# wisp-6-peripherals.net
KiCad netlist of a schematic drawn in Altium Designer
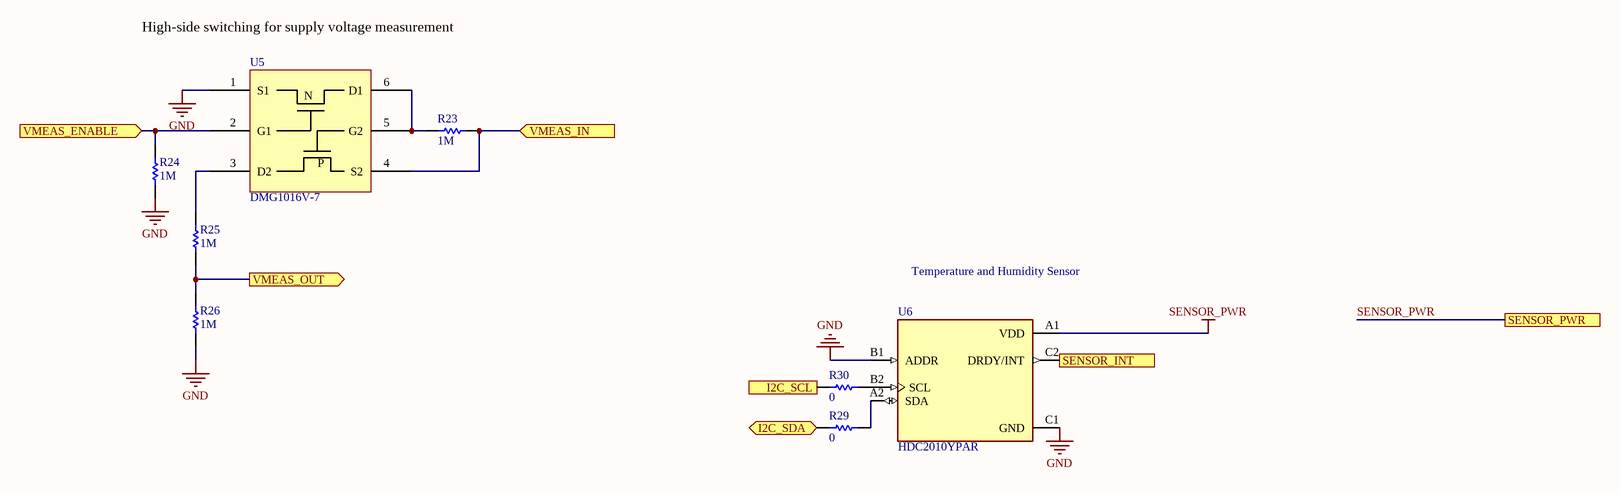
[diagram p0: wisp-6-peripherals.SchDoc]

(export (version "E")
  (design (tool "Eeschema 10.0.6"))
  (components
    (comp (ref "R23")
      (value "1M")
      (footprint "0402")
      (description "RES 1M OHM 5% 1/16W 0402")
      (fields
        (field (name "MANUFACTURER") "YAGEO")
        (field (name "MANUFACTURER PART NUMBER") "RC0402JR-071ML")
      )
      (libsource (lib "WISP6") (part "R-1M-0.063W-5%-0402"))
    )
    (comp (ref "R24")
      (value "1M")
      (footprint "0402")
      (description "RES 1M OHM 5% 1/16W 0402")
      (fields
        (field (name "MANUFACTURER") "YAGEO")
        (field (name "MANUFACTURER PART NUMBER") "RC0402JR-071ML")
      )
      (libsource (lib "WISP6") (part "R-1M-0.063W-5%-0402"))
    )
    (comp (ref "R25")
      (value "1M")
      (footprint "0402")
      (description "RES 1M OHM 5% 1/16W 0402")
      (fields
        (field (name "MANUFACTURER") "YAGEO")
        (field (name "MANUFACTURER PART NUMBER") "RC0402JR-071ML")
      )
      (libsource (lib "WISP6") (part "R-1M-0.063W-5%-0402"))
    )
    (comp (ref "R26")
      (value "1M")
      (footprint "0402")
      (description "RES 1M OHM 5% 1/16W 0402")
      (fields
        (field (name "MANUFACTURER") "YAGEO")
        (field (name "MANUFACTURER PART NUMBER") "RC0402JR-071ML")
      )
      (libsource (lib "WISP6") (part "R-1M-0.063W-5%-0402"))
    )
    (comp (ref "R29")
      (value "0")
      (footprint "0402")
      (description "RES 0 OHM JUMPER 1/16W 0402")
      (fields
        (field (name "MANUFACTURER") "YAGEO")
        (field (name "MANUFACTURER PART NUMBER") "RC0402JR-070RL")
      )
      (libsource (lib "WISP6") (part "R-0-0.063W-*-0402"))
    )
    (comp (ref "R30")
      (value "0")
      (footprint "0402")
      (description "RES 0 OHM JUMPER 1/16W 0402")
      (fields
        (field (name "MANUFACTURER") "YAGEO")
        (field (name "MANUFACTURER PART NUMBER") "RC0402JR-070RL")
      )
      (libsource (lib "WISP6") (part "R-0-0.063W-*-0402"))
    )
    (comp (ref "U5")
      (value "DMG1016V-7")
      (footprint "SOT-563 Diodes Incorporated")
      (description "MOSFET N/P-CH 20V 0.87A SOT563")
      (fields
        (field (name "MANUFACTURER") "Diodes Incorporated")
        (field (name "DIGI-KEY PART NUMBER") "DMG1016V-7DICT-ND")
      )
      (libsource (lib "WISP6") (part "DMG1016V-7"))
    )
    (comp (ref "U6")
      (value "HDC2010YPAR")
      (footprint "SnapEDApcb:BGA6C100X50P2X3_HDC2010YPAR")
      (description "Humidity, Temperature 0 ~ 100% RH I2C ±2% 8 s Surface Mount")
      (fields
        (field (name "MANUFACTURER") "Texas Instruments")
        (field (name "DIGI-KEY PART NUMBER") "296-47774-1-ND")
      )
      (libsource (lib "WISP6") (part "HDC2010YPAR"))
    )
  )
  (nets
    (net (code "1") (name "/I2C_SCL") (class "Default")
      (node (ref "R30") (pin "1") (pinfunction "1_1") (pintype "passive"))
    )
    (net (code "2") (name "/I2C_SDA") (class "Default")
      (node (ref "R29") (pin "1") (pinfunction "1_1") (pintype "passive"))
    )
    (net (code "3") (name "/SENSOR_INT") (class "Default")
      (node (ref "U6") (pin "C2") (pinfunction "DRDY/INT_C2") (pintype "output"))
    )
    (net (code "4") (name "/VMEAS_ENABLE") (class "Default")
      (node (ref "R24") (pin "2") (pinfunction "2_2") (pintype "passive"))
      (node (ref "U5") (pin "2") (pinfunction "G1_2") (pintype "passive"))
    )
    (net (code "5") (name "/VMEAS_IN") (class "Default")
      (node (ref "R23") (pin "2") (pinfunction "2_2") (pintype "passive"))
      (node (ref "U5") (pin "4") (pinfunction "S2_4") (pintype "passive"))
    )
    (net (code "6") (name "/VMEAS_OUT") (class "Default")
      (node (ref "R25") (pin "1") (pinfunction "1_1") (pintype "passive"))
      (node (ref "R26") (pin "2") (pinfunction "2_2") (pintype "passive"))
    )
    (net (code "7") (name "GND") (class "Default")
      (node (ref "R24") (pin "1") (pinfunction "1_1") (pintype "passive"))
      (node (ref "R26") (pin "1") (pinfunction "1_1") (pintype "passive"))
      (node (ref "U5") (pin "1") (pinfunction "S1_1") (pintype "passive"))
      (node (ref "U6") (pin "B1") (pinfunction "ADDR_B1") (pintype "input"))
      (node (ref "U6") (pin "C1") (pinfunction "GND_C1") (pintype "power_in"))
    )
    (net (code "8") (name "Net-(U5-D1)") (class "Default")
      (node (ref "R23") (pin "1") (pinfunction "1_1") (pintype "passive"))
      (node (ref "U5") (pin "5") (pinfunction "G2_5") (pintype "passive"))
      (node (ref "U5") (pin "6") (pinfunction "D1_6") (pintype "passive"))
    )
    (net (code "9") (name "Net-(U5-D2)") (class "Default")
      (node (ref "R25") (pin "2") (pinfunction "2_2") (pintype "passive"))
      (node (ref "U5") (pin "3") (pinfunction "D2_3") (pintype "passive"))
    )
    (net (code "10") (name "Net-(U6-SCL)") (class "Default")
      (node (ref "R30") (pin "2") (pinfunction "2_2") (pintype "passive"))
      (node (ref "U6") (pin "B2") (pinfunction "SCL_B2") (pintype "input"))
    )
    (net (code "11") (name "Net-(U6-SDA)") (class "Default")
      (node (ref "R29") (pin "2") (pinfunction "2_2") (pintype "passive"))
      (node (ref "U6") (pin "A2") (pinfunction "SDA_A2") (pintype "bidirectional"))
    )
    (net (code "12") (name "SENSOR_PWR") (class "Default")
      (node (ref "U6") (pin "A1") (pinfunction "VDD_A1") (pintype "power_in"))
    )
  )
)
